# FMU_FMU3_REV_C.net
KiCad netlist of a schematic drawn in Altium Designer
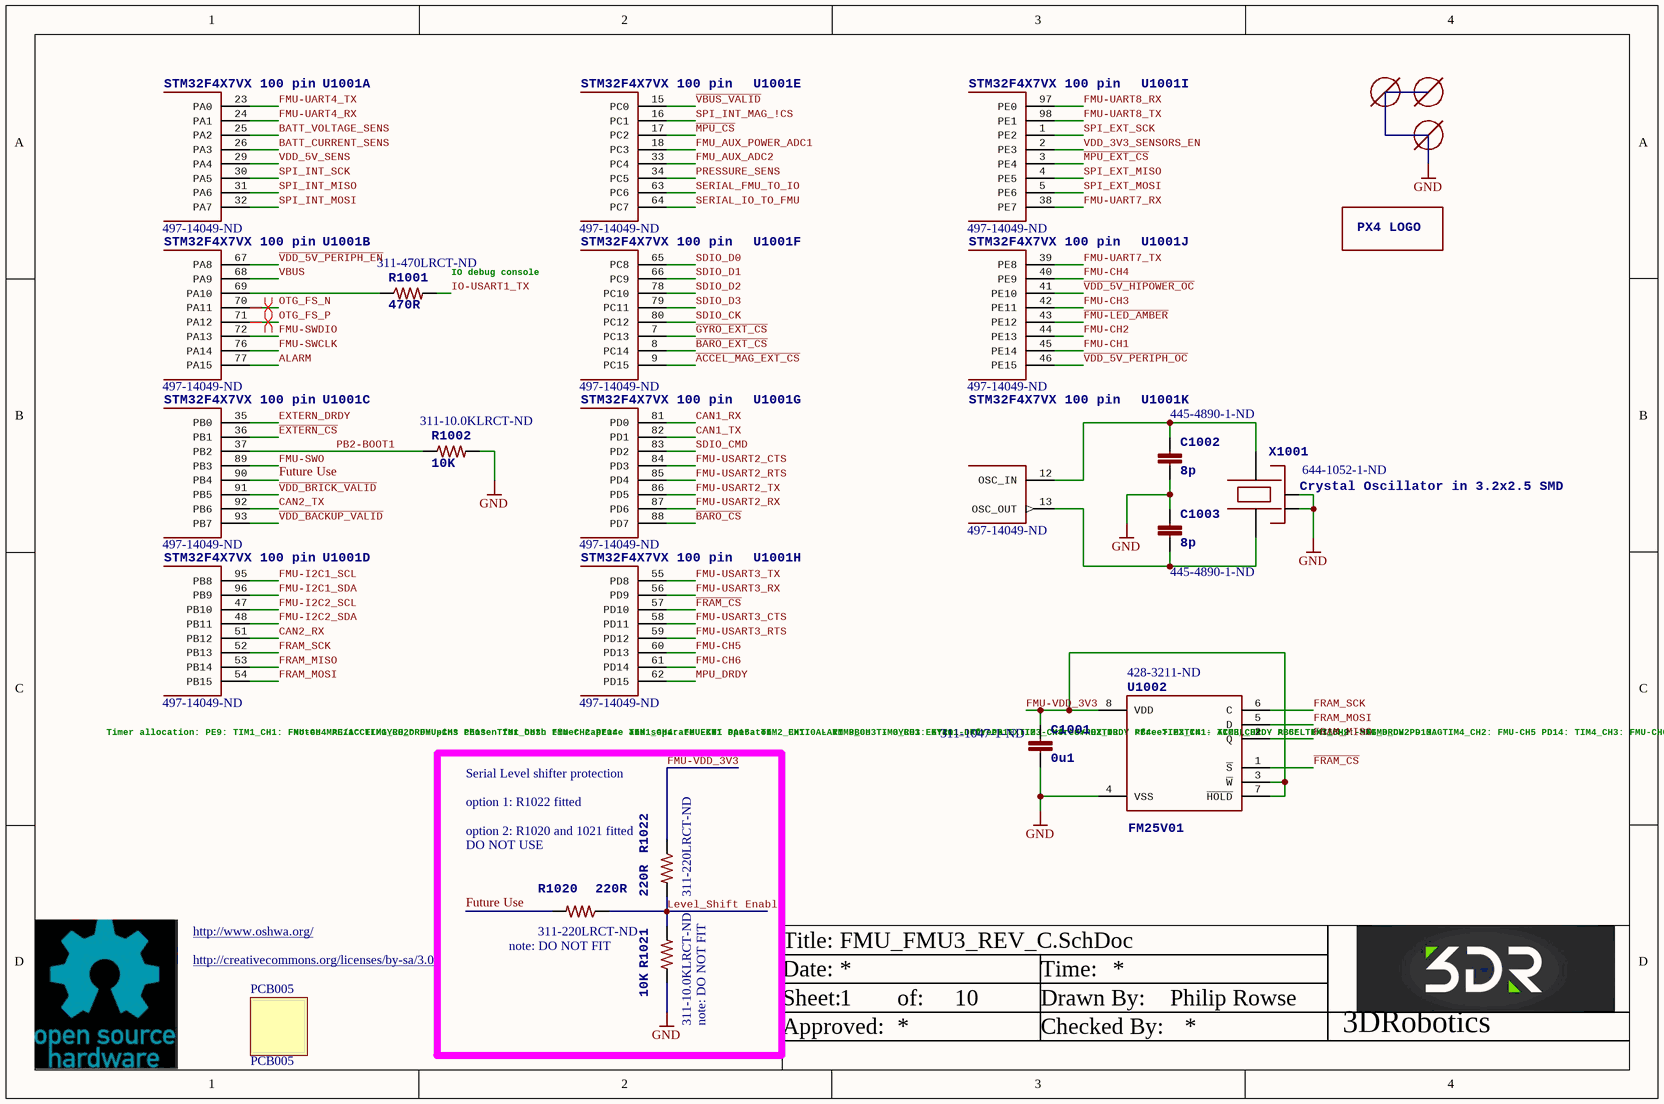
[diagram p0: FMU_FMU3_REV_C.SchDoc]

(export (version "E")
  (design (tool "Eeschema 10.0.6"))
  (components
    (comp (ref "C1001")
      (value "0u1")
      (footprint "0402-CAP")
      (description "CAP CER 0.1UF 16V Y5V 0402")
      (fields
        (field (name "PARTNO") "CC0402ZRY5V7BB104")
        (field (name "SUPPLIER PART NUMBER 1") "311-1047-1-ND")
        (field (name "3DR_PARTNO") "ECM0700")
      )
      (libsource (lib "pixhawk2") (part "CAP0402"))
    )
    (comp (ref "C1002")
      (value "8p")
      (footprint "0402-CAP")
      (description "CAP CER 8PF 50V C0G 0402")
      (fields
        (field (name "PARTNO") "C1005C0G1H080C")
        (field (name "SUPPLIER PART NUMBER 1") "445-4890-1-ND")
        (field (name "3DR_PARTNO") "ECM0710")
      )
      (libsource (lib "pixhawk2") (part "CAP0402"))
    )
    (comp (ref "C1003")
      (value "8p")
      (footprint "0402-CAP")
      (description "CAP CER 8PF 50V C0G 0402")
      (fields
        (field (name "PARTNO") "C1005C0G1H080C")
        (field (name "SUPPLIER PART NUMBER 1") "445-4890-1-ND")
        (field (name "3DR_PARTNO") "ECM0710")
      )
      (libsource (lib "pixhawk2") (part "CAP0402"))
    )
    (comp (ref "M3_MOUNT1001")
      (value "MOUNT-HOLE1.8MM")
      (footprint "MOUNT-HOLE1.8")
      (libsource (lib "pixhawk2") (part "MOUNT-HOLE1.8MM"))
    )
    (comp (ref "M3_MOUNT1003")
      (value "MOUNT-HOLE1.8MM")
      (footprint "MOUNT-HOLE1.8")
      (libsource (lib "pixhawk2") (part "MOUNT-HOLE1.8MM"))
    )
    (comp (ref "M3_MOUNT1004")
      (value "MOUNT-HOLE1.8MM")
      (footprint "MOUNT-HOLE1.8")
      (libsource (lib "pixhawk2") (part "MOUNT-HOLE1.8MM"))
    )
    (comp (ref "PCB005")
      (value "PCB005")
      (description "PCB,FMU, PX2, Board")
      (libsource (lib "lib_pixhawk") (part "PCB_0005"))
    )
    (comp (ref "R1001")
      (value "470R")
      (footprint "0402-RES")
      (description "RES 470 OHM 1/16W 1% 0402 SMD")
      (fields
        (field (name "PARTNO") "RC0402FR-07470RL")
        (field (name "SUPPLIER PART NUMBER 1") "311-470LRCT-ND")
        (field (name "3DR_PARTNO") "ECM0823")
      )
      (libsource (lib "pixhawk2") (part "RESISTOR0402-RES"))
    )
    (comp (ref "R1002")
      (value "10K")
      (footprint "0402-RES")
      (description "RES 10K OHM 1/16W 1% 0402 SMD")
      (fields
        (field (name "PARTNO") "RC0402FR-0710KL")
        (field (name "SUPPLIER PART NUMBER 1") "311-10.0KLRCT-ND")
        (field (name "3DR_PARTNO") "ECM0800")
      )
      (libsource (lib "pixhawk2") (part "RESISTOR0402-RES"))
    )
    (comp (ref "R1020")
      (value "220R")
      (footprint "0402-RES")
      (description "RES 220 OHM 1/16W 1% 0402 SMD")
      (fields
        (field (name "PARTNO") "RC0402FR-07220RL")
        (field (name "SUPPLIER PART NUMBER 1") "311-220LRCT-ND")
        (field (name "3DR_PARTNO") "ECM0821")
        (field (name "NOTE") "DO NOT FIT")
      )
      (libsource (lib "pixhawk2") (part "RESISTOR0402-RES"))
    )
    (comp (ref "R1021")
      (value "10K")
      (footprint "0402-RES")
      (description "RES 10K OHM 1/16W 1% 0402 SMD")
      (fields
        (field (name "PARTNO") "RC0402FR-0710KL")
        (field (name "SUPPLIER PART NUMBER 1") "311-10.0KLRCT-ND")
        (field (name "3DR_PARTNO") "ECM0800")
        (field (name "NOTE") "DO NOT FIT")
      )
      (libsource (lib "pixhawk2") (part "RESISTOR0402-RES"))
    )
    (comp (ref "R1022")
      (value "220R")
      (footprint "0402-RES")
      (description "RES 220 OHM 1/16W 1% 0402 SMD")
      (fields
        (field (name "PARTNO") "RC0402FR-07220RL")
        (field (name "SUPPLIER PART NUMBER 1") "311-220LRCT-ND")
        (field (name "3DR_PARTNO") "ECM0821")
      )
      (libsource (lib "pixhawk2") (part "RESISTOR0402-RES"))
    )
    (comp (ref "U$4")
      (value "PX4-LOGO-10MM")
      (footprint "PX4-LOGO-10MM")
      (fields (field (name "PX4 LOGO") "PX4 LOGO"))
      (libsource (lib "pixhawk2") (part "PX4-LOGO-10MM"))
    )
    (comp (ref "U1001")
      (value "STM32F4X7VX 100 pin")
      (footprint "TQFP100")
      (description "REV 3 Silicon or later IC MCU ARM 2MB FLASH 100LQFP")
      (fields (field (name "SUPPLIER PART NUMBER 1") "497-14049-ND") (field (name "3DR_PARTNO") "ECM0841"))
      (libsource (lib "pixhawk2") (part "STM32F4X7VX"))
    )
    (comp (ref "U1002")
      (value "FM25V01")
      (footprint "SO08")
      (description "IC FRAM 128KBIT 40MHZ 8SOIC")
      (fields
        (field (name "PARTNO") "FM25V01-G")
        (field (name "SUPPLIER PART NUMBER 1") "428-3211-ND")
        (field (name "3DR_PARTNO") "ECM0826")
      )
      (libsource (lib "pixhawk2") (part "FM25V01"))
    )
    (comp (ref "X1001")
      (value "Crystal Oscillator in 3.2x2.5 SMD")
      (footprint "OSCILLATOR-3.2X2.5")
      (description "CRYSTAL 24MHZ 8PF SMD")
      (fields
        (field (name "SUPPLIER PART NUMBER 1") "644-1052-1-ND")
        (field (name "3DR_PARTNO") "ECM0708")
        (field (name "PARTNO") "NX3225SA-24.000MHZ-STD-CSR-1")
      )
      (libsource (lib "pixhawk2") (part "OSCILLATOR-3.2X2.5"))
    )
  )
  (nets
    (net (code "1") (name "/ALARM") (class "Default")
      (node (ref "U1001") (pin "77") (pinfunction "PA15_77") (pintype "passive"))
    )
    (net (code "2") (name "/BATT_CURRENT_SENS") (class "Default")
      (node (ref "U1001") (pin "26") (pinfunction "PA3_26") (pintype "passive"))
    )
    (net (code "3") (name "/BATT_VOLTAGE_SENS") (class "Default")
      (node (ref "U1001") (pin "25") (pinfunction "PA2_25") (pintype "passive"))
    )
    (net (code "4") (name "/CAN1_RX") (class "Default")
      (node (ref "U1001") (pin "81") (pinfunction "PD0_81") (pintype "passive"))
    )
    (net (code "5") (name "/CAN1_TX") (class "Default")
      (node (ref "U1001") (pin "82") (pinfunction "PD1_82") (pintype "passive"))
    )
    (net (code "6") (name "/CAN2_RX") (class "Default")
      (node (ref "U1001") (pin "51") (pinfunction "PB12_51") (pintype "passive"))
    )
    (net (code "7") (name "/CAN2_TX") (class "Default")
      (node (ref "U1001") (pin "92") (pinfunction "PB6_92") (pintype "passive"))
    )
    (net (code "8") (name "/EXTERN_DRDY") (class "Default")
      (node (ref "U1001") (pin "35") (pinfunction "PB0_35") (pintype "passive"))
    )
    (net (code "9") (name "/FMU-CH1") (class "Default")
      (node (ref "U1001") (pin "45") (pinfunction "PE14_45") (pintype "passive"))
    )
    (net (code "10") (name "/FMU-CH2") (class "Default")
      (node (ref "U1001") (pin "44") (pinfunction "PE13_44") (pintype "passive"))
    )
    (net (code "11") (name "/FMU-CH3") (class "Default")
      (node (ref "U1001") (pin "42") (pinfunction "PE11_42") (pintype "passive"))
    )
    (net (code "12") (name "/FMU-CH4") (class "Default")
      (node (ref "U1001") (pin "40") (pinfunction "PE9_40") (pintype "passive"))
    )
    (net (code "13") (name "/FMU-CH5") (class "Default")
      (node (ref "U1001") (pin "60") (pinfunction "PD13_60") (pintype "passive"))
    )
    (net (code "14") (name "/FMU-CH6") (class "Default")
      (node (ref "U1001") (pin "61") (pinfunction "PD14_61") (pintype "passive"))
    )
    (net (code "15") (name "/FMU-I2C1_SCL") (class "Default")
      (node (ref "U1001") (pin "95") (pinfunction "PB8_95") (pintype "passive"))
    )
    (net (code "16") (name "/FMU-I2C1_SDA") (class "Default")
      (node (ref "U1001") (pin "96") (pinfunction "PB9_96") (pintype "passive"))
    )
    (net (code "17") (name "/FMU-I2C2_SCL") (class "Default")
      (node (ref "U1001") (pin "47") (pinfunction "PB10_47") (pintype "passive"))
    )
    (net (code "18") (name "/FMU-I2C2_SDA") (class "Default")
      (node (ref "U1001") (pin "48") (pinfunction "PB11_48") (pintype "passive"))
    )
    (net (code "19") (name "/FMU-SWCLK") (class "Default")
      (node (ref "U1001") (pin "76") (pinfunction "PA14_76") (pintype "passive"))
    )
    (net (code "20") (name "/FMU-SWDIO") (class "Default")
      (node (ref "U1001") (pin "72") (pinfunction "PA13_72") (pintype "passive"))
    )
    (net (code "21") (name "/FMU-SWO") (class "Default")
      (node (ref "U1001") (pin "89") (pinfunction "PB3_89") (pintype "passive"))
    )
    (net (code "22") (name "/FMU-UART4_RX") (class "Default")
      (node (ref "U1001") (pin "24") (pinfunction "PA1_24") (pintype "passive"))
    )
    (net (code "23") (name "/FMU-UART4_TX") (class "Default")
      (node (ref "U1001") (pin "23") (pinfunction "PA0_23") (pintype "passive"))
    )
    (net (code "24") (name "/FMU-UART7_RX") (class "Default")
      (node (ref "U1001") (pin "38") (pinfunction "PE7_38") (pintype "passive"))
    )
    (net (code "25") (name "/FMU-UART7_TX") (class "Default")
      (node (ref "U1001") (pin "39") (pinfunction "PE8_39") (pintype "passive"))
    )
    (net (code "26") (name "/FMU-UART8_RX") (class "Default")
      (node (ref "U1001") (pin "97") (pinfunction "PE0_97") (pintype "passive"))
    )
    (net (code "27") (name "/FMU-UART8_TX") (class "Default")
      (node (ref "U1001") (pin "98") (pinfunction "PE1_98") (pintype "passive"))
    )
    (net (code "28") (name "/FMU-USART2_CTS") (class "Default")
      (node (ref "U1001") (pin "84") (pinfunction "PD3_84") (pintype "passive"))
    )
    (net (code "29") (name "/FMU-USART2_RTS") (class "Default")
      (node (ref "U1001") (pin "85") (pinfunction "PD4_85") (pintype "passive"))
    )
    (net (code "30") (name "/FMU-USART2_RX") (class "Default")
      (node (ref "U1001") (pin "87") (pinfunction "PD6_87") (pintype "passive"))
    )
    (net (code "31") (name "/FMU-USART2_TX") (class "Default")
      (node (ref "U1001") (pin "86") (pinfunction "PD5_86") (pintype "passive"))
    )
    (net (code "32") (name "/FMU-USART3_CTS") (class "Default")
      (node (ref "U1001") (pin "58") (pinfunction "PD11_58") (pintype "passive"))
    )
    (net (code "33") (name "/FMU-USART3_RTS") (class "Default")
      (node (ref "U1001") (pin "59") (pinfunction "PD12_59") (pintype "passive"))
    )
    (net (code "34") (name "/FMU-USART3_RX") (class "Default")
      (node (ref "U1001") (pin "56") (pinfunction "PD9_56") (pintype "passive"))
    )
    (net (code "35") (name "/FMU-USART3_TX") (class "Default")
      (node (ref "U1001") (pin "55") (pinfunction "PD8_55") (pintype "passive"))
    )
    (net (code "36") (name "/FMU-VDD_3V3") (class "Default")
      (node (ref "C1001") (pin "P$1") (pinfunction "1_P$1") (pintype "passive"))
      (node (ref "R1022") (pin "P$1") (pinfunction "1_P$1") (pintype "passive"))
      (node (ref "U1002") (pin "3") (pinfunction "~{W}_3") (pintype "passive"))
      (node (ref "U1002") (pin "7") (pinfunction "~{HOLD}_7") (pintype "passive"))
      (node (ref "U1002") (pin "8") (pinfunction "VDD_8") (pintype "passive"))
    )
    (net (code "37") (name "/FMU_AUX_ADC2") (class "Default")
      (node (ref "U1001") (pin "33") (pinfunction "PC4_33") (pintype "passive"))
    )
    (net (code "38") (name "/FMU_AUX_POWER_ADC1") (class "Default")
      (node (ref "U1001") (pin "18") (pinfunction "PC3_18") (pintype "passive"))
    )
    (net (code "39") (name "/FRAM_MISO") (class "Default")
      (node (ref "U1001") (pin "53") (pinfunction "PB14_53") (pintype "passive"))
      (node (ref "U1002") (pin "2") (pinfunction "Q_2") (pintype "passive"))
    )
    (net (code "40") (name "/FRAM_MOSI") (class "Default")
      (node (ref "U1001") (pin "54") (pinfunction "PB15_54") (pintype "passive"))
      (node (ref "U1002") (pin "5") (pinfunction "D_5") (pintype "passive"))
    )
    (net (code "41") (name "/FRAM_SCK") (class "Default")
      (node (ref "U1001") (pin "52") (pinfunction "PB13_52") (pintype "passive"))
      (node (ref "U1002") (pin "6") (pinfunction "C_6") (pintype "passive"))
    )
    (net (code "42") (name "/Future Use") (class "Default")
      (node (ref "R1020") (pin "P$2") (pinfunction "2_P$2") (pintype "passive"))
      (node (ref "U1001") (pin "90") (pinfunction "PB4_90") (pintype "passive"))
    )
    (net (code "43") (name "/IO-USART1_TX") (class "Default")
      (node (ref "R1001") (pin "P$2") (pinfunction "2_P$2") (pintype "passive"))
    )
    (net (code "44") (name "/Level_Shift Enable") (class "Default")
      (node (ref "R1020") (pin "P$1") (pinfunction "1_P$1") (pintype "passive"))
      (node (ref "R1021") (pin "P$2") (pinfunction "2_P$2") (pintype "passive"))
      (node (ref "R1022") (pin "P$2") (pinfunction "2_P$2") (pintype "passive"))
    )
    (net (code "45") (name "/MPU_DRDY") (class "Default")
      (node (ref "U1001") (pin "62") (pinfunction "PD15_62") (pintype "passive"))
    )
    (net (code "46") (name "/OTG_FS_N") (class "Default")
      (node (ref "U1001") (pin "70") (pinfunction "PA11_70") (pintype "passive"))
    )
    (net (code "47") (name "/OTG_FS_P") (class "Default")
      (node (ref "U1001") (pin "71") (pinfunction "PA12_71") (pintype "passive"))
    )
    (net (code "48") (name "/PB2-BOOT1") (class "Default")
      (node (ref "R1002") (pin "P$1") (pinfunction "1_P$1") (pintype "passive"))
      (node (ref "U1001") (pin "37") (pinfunction "PB2_37") (pintype "passive"))
    )
    (net (code "49") (name "/PRESSURE_SENS") (class "Default")
      (node (ref "U1001") (pin "34") (pinfunction "PC5_34") (pintype "passive"))
    )
    (net (code "50") (name "/SDIO_CK") (class "Default")
      (node (ref "U1001") (pin "80") (pinfunction "PC12_80") (pintype "passive"))
    )
    (net (code "51") (name "/SDIO_CMD") (class "Default")
      (node (ref "U1001") (pin "83") (pinfunction "PD2_83") (pintype "passive"))
    )
    (net (code "52") (name "/SDIO_D0") (class "Default")
      (node (ref "U1001") (pin "65") (pinfunction "PC8_65") (pintype "passive"))
    )
    (net (code "53") (name "/SDIO_D1") (class "Default")
      (node (ref "U1001") (pin "66") (pinfunction "PC9_66") (pintype "passive"))
    )
    (net (code "54") (name "/SDIO_D2") (class "Default")
      (node (ref "U1001") (pin "78") (pinfunction "PC10_78") (pintype "passive"))
    )
    (net (code "55") (name "/SDIO_D3") (class "Default")
      (node (ref "U1001") (pin "79") (pinfunction "PC11_79") (pintype "passive"))
    )
    (net (code "56") (name "/SERIAL_FMU_TO_IO") (class "Default")
      (node (ref "U1001") (pin "63") (pinfunction "PC6_63") (pintype "passive"))
    )
    (net (code "57") (name "/SERIAL_IO_TO_FMU") (class "Default")
      (node (ref "U1001") (pin "64") (pinfunction "PC7_64") (pintype "passive"))
    )
    (net (code "58") (name "/SPI_EXT_MISO") (class "Default")
      (node (ref "U1001") (pin "4") (pinfunction "PE5_4") (pintype "passive"))
    )
    (net (code "59") (name "/SPI_EXT_MOSI") (class "Default")
      (node (ref "U1001") (pin "5") (pinfunction "PE6_5") (pintype "passive"))
    )
    (net (code "60") (name "/SPI_EXT_SCK") (class "Default")
      (node (ref "U1001") (pin "1") (pinfunction "PE2_1") (pintype "passive"))
    )
    (net (code "61") (name "/SPI_INT_MAG_!CS") (class "Default")
      (node (ref "U1001") (pin "16") (pinfunction "PC1_16") (pintype "passive"))
    )
    (net (code "62") (name "/SPI_INT_MISO") (class "Default")
      (node (ref "U1001") (pin "31") (pinfunction "PA6_31") (pintype "passive"))
    )
    (net (code "63") (name "/SPI_INT_MOSI") (class "Default")
      (node (ref "U1001") (pin "32") (pinfunction "PA7_32") (pintype "passive"))
    )
    (net (code "64") (name "/SPI_INT_SCK") (class "Default")
      (node (ref "U1001") (pin "30") (pinfunction "PA5_30") (pintype "passive"))
    )
    (net (code "65") (name "/VBUS") (class "Default")
      (node (ref "U1001") (pin "68") (pinfunction "PA9_68") (pintype "passive"))
    )
    (net (code "66") (name "/VDD_3V3_SENSORS_EN") (class "Default")
      (node (ref "U1001") (pin "2") (pinfunction "PE3_2") (pintype "passive"))
    )
    (net (code "67") (name "/VDD_5V_SENS") (class "Default")
      (node (ref "U1001") (pin "29") (pinfunction "PA4_29") (pintype "passive"))
    )
    (net (code "68") (name "/~{ACCEL_MAG_EXT_CS}") (class "Default")
      (node (ref "U1001") (pin "9") (pinfunction "PC15_9") (pintype "passive"))
    )
    (net (code "69") (name "/~{BARO_CS}") (class "Default")
      (node (ref "U1001") (pin "88") (pinfunction "PD7_88") (pintype "passive"))
    )
    (net (code "70") (name "/~{BARO_EXT_CS}") (class "Default")
      (node (ref "U1001") (pin "8") (pinfunction "PC14_8") (pintype "passive"))
    )
    (net (code "71") (name "/~{EXTERN_CS}") (class "Default")
      (node (ref "U1001") (pin "36") (pinfunction "PB1_36") (pintype "passive"))
    )
    (net (code "72") (name "/~{FMU-LED_AMBER}") (class "Default")
      (node (ref "U1001") (pin "43") (pinfunction "PE12_43") (pintype "passive"))
    )
    (net (code "73") (name "/~{FRAM_CS}") (class "Default")
      (node (ref "U1001") (pin "57") (pinfunction "PD10_57") (pintype "passive"))
      (node (ref "U1002") (pin "1") (pinfunction "~{S}_1") (pintype "passive"))
    )
    (net (code "74") (name "/~{GYRO_EXT_CS}") (class "Default")
      (node (ref "U1001") (pin "7") (pinfunction "PC13_7") (pintype "passive"))
    )
    (net (code "75") (name "/~{MPU_CS}") (class "Default")
      (node (ref "U1001") (pin "17") (pinfunction "PC2_17") (pintype "passive"))
    )
    (net (code "76") (name "/~{MPU_EXT_CS}") (class "Default")
      (node (ref "U1001") (pin "3") (pinfunction "PE4_3") (pintype "passive"))
    )
    (net (code "77") (name "/~{VBUS_VALID}") (class "Default")
      (node (ref "U1001") (pin "15") (pinfunction "PC0_15") (pintype "passive"))
    )
    (net (code "78") (name "/~{VDD_5V_HIPOWER_OC}") (class "Default")
      (node (ref "U1001") (pin "41") (pinfunction "PE10_41") (pintype "passive"))
    )
    (net (code "79") (name "/~{VDD_5V_PERIPH_EN}") (class "Default")
      (node (ref "U1001") (pin "67") (pinfunction "PA8_67") (pintype "passive"))
    )
    (net (code "80") (name "/~{VDD_5V_PERIPH_OC}") (class "Default")
      (node (ref "U1001") (pin "46") (pinfunction "PE15_46") (pintype "passive"))
    )
    (net (code "81") (name "/~{VDD_BACKUP_VALID}") (class "Default")
      (node (ref "U1001") (pin "93") (pinfunction "PB7_93") (pintype "passive"))
    )
    (net (code "82") (name "/~{VDD_BRICK_VALID}") (class "Default")
      (node (ref "U1001") (pin "91") (pinfunction "PB5_91") (pintype "passive"))
    )
    (net (code "83") (name "GND") (class "Default")
      (node (ref "C1001") (pin "P$2") (pinfunction "2_P$2") (pintype "passive"))
      (node (ref "C1002") (pin "P$2") (pinfunction "2_P$2") (pintype "passive"))
      (node (ref "C1003") (pin "P$1") (pinfunction "1_P$1") (pintype "passive"))
      (node (ref "R1002") (pin "P$2") (pinfunction "2_P$2") (pintype "passive"))
      (node (ref "R1021") (pin "P$1") (pinfunction "1_P$1") (pintype "passive"))
      (node (ref "U1002") (pin "4") (pinfunction "VSS_4") (pintype "passive"))
      (node (ref "X1001") (pin "2") (pinfunction "NC_2_2") (pintype "open_emitter"))
      (node (ref "X1001") (pin "4") (pinfunction "NC_4_4") (pintype "open_emitter"))
    )
    (net (code "84") (name "Net-(C1002-1)") (class "Default")
      (node (ref "C1002") (pin "P$1") (pinfunction "1_P$1") (pintype "passive"))
      (node (ref "U1001") (pin "12") (pinfunction "OSC_IN_12") (pintype "passive"))
      (node (ref "X1001") (pin "3") (pinfunction "3_3") (pintype "passive"))
    )
    (net (code "85") (name "Net-(C1003-2)") (class "Default")
      (node (ref "C1003") (pin "P$2") (pinfunction "2_P$2") (pintype "passive"))
      (node (ref "U1001") (pin "13") (pinfunction "OSC_OUT_13") (pintype "output"))
      (node (ref "X1001") (pin "1") (pinfunction "1_1") (pintype "passive"))
    )
    (net (code "86") (name "Net-(R1001-1)") (class "Default")
      (node (ref "R1001") (pin "P$1") (pinfunction "1_P$1") (pintype "passive"))
      (node (ref "U1001") (pin "69") (pinfunction "PA10_69") (pintype "passive"))
    )
  )
)
